# sch.net
KiCad netlist of a schematic drawn in EAGLE
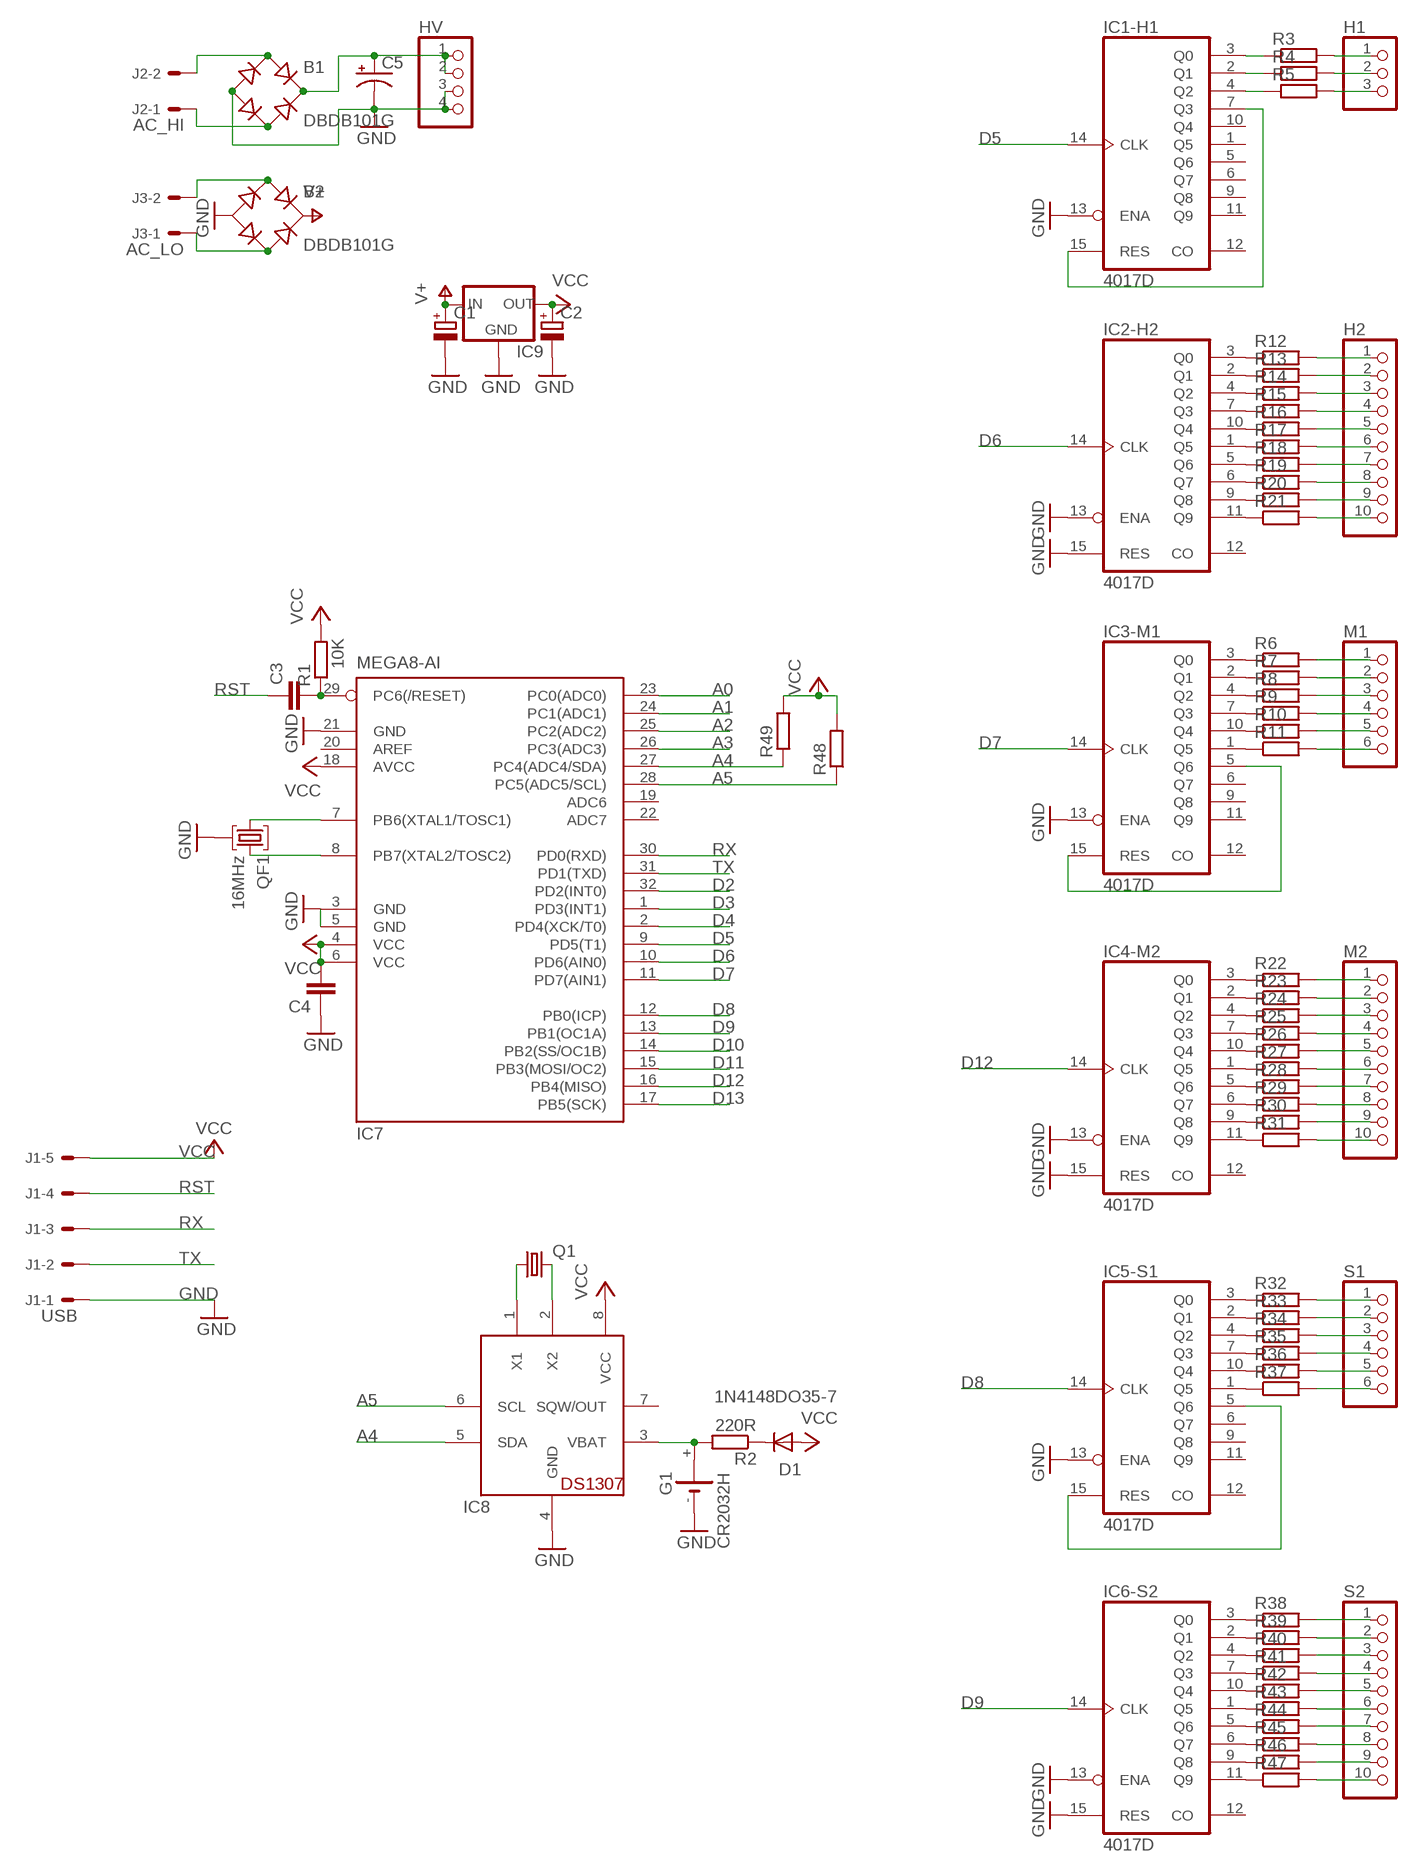
[diagram p0: schematic, sheet 1]

(export (version "E")
  (design (tool "Eeschema 10.0.6"))
  (components
    (comp (ref "B1")
      (value "DBDB101G")
      (footprint "eagle-import:DB")
      (libsource (lib "eagle-import") (part "DB?GDB101"))
    )
    (comp (ref "B2")
      (value "DBDB101G")
      (footprint "eagle-import:DB")
      (libsource (lib "eagle-import") (part "DB?GDB101"))
    )
    (comp (ref "C1")
      (value "CPOL-EU140CLH-1010")
      (footprint "eagle-import:140CLH-1010")
      (libsource (lib "eagle-import") (part "CPOL-EU140CLH-1010"))
    )
    (comp (ref "C2")
      (value "CPOL-EU140CLH-1010")
      (footprint "eagle-import:140CLH-1010")
      (libsource (lib "eagle-import") (part "CPOL-EU140CLH-1010"))
    )
    (comp (ref "C3")
      (value "C-EUC1206K")
      (footprint "eagle-import:C1206K")
      (libsource (lib "eagle-import") (part "C-EUC1206K"))
    )
    (comp (ref "C4")
      (value "C-EUC1206K")
      (footprint "eagle-import:C1206K")
      (libsource (lib "eagle-import") (part "C-EUC1206K"))
    )
    (comp (ref "C5")
      (value "CPOL-USE5-13")
      (footprint "eagle-import:E5-13")
      (libsource (lib "eagle-import") (part "CPOL-USE5-13"))
    )
    (comp (ref "D1")
      (value "1N4148DO35-7")
      (footprint "eagle-import:DO35-7")
      (libsource (lib "eagle-import") (part "1N4148DO35-7"))
    )
    (comp (ref "G1")
      (value "CR2032H")
      (footprint "eagle-import:CR2032H")
      (libsource (lib "eagle-import") (part "CR2032H"))
    )
    (comp (ref "H1")
      (value "PINHD-1X3")
      (footprint "eagle-import:1X03")
      (libsource (lib "eagle-import") (part "PINHD-1X3"))
    )
    (comp (ref "H2")
      (value "PINHD-1X10")
      (footprint "eagle-import:1X10")
      (libsource (lib "eagle-import") (part "PINHD-1X10"))
    )
    (comp (ref "HV")
      (value "PINHD-1X4")
      (footprint "eagle-import:1X04")
      (libsource (lib "eagle-import") (part "PINHD-1X4"))
    )
    (comp (ref "IC1-H1")
      (value "4017D")
      (footprint "eagle-import:SO16")
      (libsource (lib "eagle-import") (part "4017D"))
    )
    (comp (ref "IC2-H2")
      (value "4017D")
      (footprint "eagle-import:SO16")
      (libsource (lib "eagle-import") (part "4017D"))
    )
    (comp (ref "IC3-M1")
      (value "4017D")
      (footprint "eagle-import:SO16")
      (libsource (lib "eagle-import") (part "4017D"))
    )
    (comp (ref "IC4-M2")
      (value "4017D")
      (footprint "eagle-import:SO16")
      (libsource (lib "eagle-import") (part "4017D"))
    )
    (comp (ref "IC5-S1")
      (value "4017D")
      (footprint "eagle-import:SO16")
      (libsource (lib "eagle-import") (part "4017D"))
    )
    (comp (ref "IC6-S2")
      (value "4017D")
      (footprint "eagle-import:SO16")
      (libsource (lib "eagle-import") (part "4017D"))
    )
    (comp (ref "IC7")
      (value "MEGA8-AI")
      (footprint "eagle-import:TQFP32-08")
      (fields (field (name "MPN") "ATMEGA8-16AU"))
      (libsource (lib "eagle-import") (part "MEGA8-AI"))
    )
    (comp (ref "IC8")
      (value "DS1307")
      (footprint "eagle-import:DIL08")
      (libsource (lib "eagle-import") (part "DS1307"))
    )
    (comp (ref "IC9")
      (value "78XXS")
      (footprint "eagle-import:78XXS")
      (libsource (lib "eagle-import") (part "78XXS"))
    )
    (comp (ref "J1")
      (value "USB")
      (footprint "eagle-import:7395-05")
      (libsource (lib "eagle-import") (part "22-?-0505-7058"))
    )
    (comp (ref "J2")
      (value "AC_HI")
      (footprint "eagle-import:7395-02")
      (libsource (lib "eagle-import") (part "22-?-0205-7028"))
    )
    (comp (ref "J3")
      (value "AC_LO")
      (footprint "eagle-import:7395-02")
      (libsource (lib "eagle-import") (part "22-?-0205-7028"))
    )
    (comp (ref "M1")
      (value "PINHD-1X6")
      (footprint "eagle-import:1X06")
      (libsource (lib "eagle-import") (part "PINHD-1X6"))
    )
    (comp (ref "M2")
      (value "PINHD-1X10")
      (footprint "eagle-import:1X10")
      (libsource (lib "eagle-import") (part "PINHD-1X10"))
    )
    (comp (ref "Q1")
      (value "CRYSTALTC26H")
      (footprint "eagle-import:TC26H")
      (libsource (lib "eagle-import") (part "CRYSTALTC26H"))
    )
    (comp (ref "QF1")
      (value "16MHz")
      (footprint "eagle-import:HC49U")
      (libsource (lib "eagle-import") (part "8M10AHC49T"))
    )
    (comp (ref "R1")
      (value "10K")
      (footprint "eagle-import:0207_7")
      (libsource (lib "eagle-import") (part "R-EU_0207/7"))
    )
    (comp (ref "R2")
      (value "220R")
      (footprint "eagle-import:0207_7")
      (libsource (lib "eagle-import") (part "R-EU_0207/7"))
    )
    (comp (ref "R3")
      (value "R-EU_0204/5")
      (footprint "eagle-import:0204_5")
      (libsource (lib "eagle-import") (part "R-EU_0204/5"))
    )
    (comp (ref "R4")
      (value "R-EU_0204/5")
      (footprint "eagle-import:0204_5")
      (libsource (lib "eagle-import") (part "R-EU_0204/5"))
    )
    (comp (ref "R5")
      (value "R-EU_0204/5")
      (footprint "eagle-import:0204_5")
      (libsource (lib "eagle-import") (part "R-EU_0204/5"))
    )
    (comp (ref "R6")
      (value "R-EU_0204/5")
      (footprint "eagle-import:0204_5")
      (libsource (lib "eagle-import") (part "R-EU_0204/5"))
    )
    (comp (ref "R7")
      (value "R-EU_0204/5")
      (footprint "eagle-import:0204_5")
      (libsource (lib "eagle-import") (part "R-EU_0204/5"))
    )
    (comp (ref "R8")
      (value "R-EU_0204/5")
      (footprint "eagle-import:0204_5")
      (libsource (lib "eagle-import") (part "R-EU_0204/5"))
    )
    (comp (ref "R9")
      (value "R-EU_0204/5")
      (footprint "eagle-import:0204_5")
      (libsource (lib "eagle-import") (part "R-EU_0204/5"))
    )
    (comp (ref "R10")
      (value "R-EU_0204/5")
      (footprint "eagle-import:0204_5")
      (libsource (lib "eagle-import") (part "R-EU_0204/5"))
    )
    (comp (ref "R11")
      (value "R-EU_0204/5")
      (footprint "eagle-import:0204_5")
      (libsource (lib "eagle-import") (part "R-EU_0204/5"))
    )
    (comp (ref "R12")
      (value "R-EU_0204/5")
      (footprint "eagle-import:0204_5")
      (libsource (lib "eagle-import") (part "R-EU_0204/5"))
    )
    (comp (ref "R13")
      (value "R-EU_0204/5")
      (footprint "eagle-import:0204_5")
      (libsource (lib "eagle-import") (part "R-EU_0204/5"))
    )
    (comp (ref "R14")
      (value "R-EU_0204/5")
      (footprint "eagle-import:0204_5")
      (libsource (lib "eagle-import") (part "R-EU_0204/5"))
    )
    (comp (ref "R15")
      (value "R-EU_0204/5")
      (footprint "eagle-import:0204_5")
      (libsource (lib "eagle-import") (part "R-EU_0204/5"))
    )
    (comp (ref "R16")
      (value "R-EU_0204/5")
      (footprint "eagle-import:0204_5")
      (libsource (lib "eagle-import") (part "R-EU_0204/5"))
    )
    (comp (ref "R17")
      (value "R-EU_0204/5")
      (footprint "eagle-import:0204_5")
      (libsource (lib "eagle-import") (part "R-EU_0204/5"))
    )
    (comp (ref "R18")
      (value "R-EU_0204/5")
      (footprint "eagle-import:0204_5")
      (libsource (lib "eagle-import") (part "R-EU_0204/5"))
    )
    (comp (ref "R19")
      (value "R-EU_0204/5")
      (footprint "eagle-import:0204_5")
      (libsource (lib "eagle-import") (part "R-EU_0204/5"))
    )
    (comp (ref "R20")
      (value "R-EU_0204/5")
      (footprint "eagle-import:0204_5")
      (libsource (lib "eagle-import") (part "R-EU_0204/5"))
    )
    (comp (ref "R21")
      (value "R-EU_0204/5")
      (footprint "eagle-import:0204_5")
      (libsource (lib "eagle-import") (part "R-EU_0204/5"))
    )
    (comp (ref "R22")
      (value "R-EU_0204/5")
      (footprint "eagle-import:0204_5")
      (libsource (lib "eagle-import") (part "R-EU_0204/5"))
    )
    (comp (ref "R23")
      (value "R-EU_0204/5")
      (footprint "eagle-import:0204_5")
      (libsource (lib "eagle-import") (part "R-EU_0204/5"))
    )
    (comp (ref "R24")
      (value "R-EU_0204/5")
      (footprint "eagle-import:0204_5")
      (libsource (lib "eagle-import") (part "R-EU_0204/5"))
    )
    (comp (ref "R25")
      (value "R-EU_0204/5")
      (footprint "eagle-import:0204_5")
      (libsource (lib "eagle-import") (part "R-EU_0204/5"))
    )
    (comp (ref "R26")
      (value "R-EU_0204/5")
      (footprint "eagle-import:0204_5")
      (libsource (lib "eagle-import") (part "R-EU_0204/5"))
    )
    (comp (ref "R27")
      (value "R-EU_0204/5")
      (footprint "eagle-import:0204_5")
      (libsource (lib "eagle-import") (part "R-EU_0204/5"))
    )
    (comp (ref "R28")
      (value "R-EU_0204/5")
      (footprint "eagle-import:0204_5")
      (libsource (lib "eagle-import") (part "R-EU_0204/5"))
    )
    (comp (ref "R29")
      (value "R-EU_0204/5")
      (footprint "eagle-import:0204_5")
      (libsource (lib "eagle-import") (part "R-EU_0204/5"))
    )
    (comp (ref "R30")
      (value "R-EU_0204/5")
      (footprint "eagle-import:0204_5")
      (libsource (lib "eagle-import") (part "R-EU_0204/5"))
    )
    (comp (ref "R31")
      (value "R-EU_0204/5")
      (footprint "eagle-import:0204_5")
      (libsource (lib "eagle-import") (part "R-EU_0204/5"))
    )
    (comp (ref "R32")
      (value "R-EU_0204/5")
      (footprint "eagle-import:0204_5")
      (libsource (lib "eagle-import") (part "R-EU_0204/5"))
    )
    (comp (ref "R33")
      (value "R-EU_0204/5")
      (footprint "eagle-import:0204_5")
      (libsource (lib "eagle-import") (part "R-EU_0204/5"))
    )
    (comp (ref "R34")
      (value "R-EU_0204/5")
      (footprint "eagle-import:0204_5")
      (libsource (lib "eagle-import") (part "R-EU_0204/5"))
    )
    (comp (ref "R35")
      (value "R-EU_0204/5")
      (footprint "eagle-import:0204_5")
      (libsource (lib "eagle-import") (part "R-EU_0204/5"))
    )
    (comp (ref "R36")
      (value "R-EU_0204/5")
      (footprint "eagle-import:0204_5")
      (libsource (lib "eagle-import") (part "R-EU_0204/5"))
    )
    (comp (ref "R37")
      (value "R-EU_0204/5")
      (footprint "eagle-import:0204_5")
      (libsource (lib "eagle-import") (part "R-EU_0204/5"))
    )
    (comp (ref "R38")
      (value "R-EU_0204/5")
      (footprint "eagle-import:0204_5")
      (libsource (lib "eagle-import") (part "R-EU_0204/5"))
    )
    (comp (ref "R39")
      (value "R-EU_0204/5")
      (footprint "eagle-import:0204_5")
      (libsource (lib "eagle-import") (part "R-EU_0204/5"))
    )
    (comp (ref "R40")
      (value "R-EU_0204/5")
      (footprint "eagle-import:0204_5")
      (libsource (lib "eagle-import") (part "R-EU_0204/5"))
    )
    (comp (ref "R41")
      (value "R-EU_0204/5")
      (footprint "eagle-import:0204_5")
      (libsource (lib "eagle-import") (part "R-EU_0204/5"))
    )
    (comp (ref "R42")
      (value "R-EU_0204/5")
      (footprint "eagle-import:0204_5")
      (libsource (lib "eagle-import") (part "R-EU_0204/5"))
    )
    (comp (ref "R43")
      (value "R-EU_0204/5")
      (footprint "eagle-import:0204_5")
      (libsource (lib "eagle-import") (part "R-EU_0204/5"))
    )
    (comp (ref "R44")
      (value "R-EU_0204/5")
      (footprint "eagle-import:0204_5")
      (libsource (lib "eagle-import") (part "R-EU_0204/5"))
    )
    (comp (ref "R45")
      (value "R-EU_0204/5")
      (footprint "eagle-import:0204_5")
      (libsource (lib "eagle-import") (part "R-EU_0204/5"))
    )
    (comp (ref "R46")
      (value "R-EU_0204/5")
      (footprint "eagle-import:0204_5")
      (libsource (lib "eagle-import") (part "R-EU_0204/5"))
    )
    (comp (ref "R47")
      (value "R-EU_0204/5")
      (footprint "eagle-import:0204_5")
      (libsource (lib "eagle-import") (part "R-EU_0204/5"))
    )
    (comp (ref "R48")
      (value "R-EU_0204/5")
      (footprint "eagle-import:0204_5")
      (libsource (lib "eagle-import") (part "R-EU_0204/5"))
    )
    (comp (ref "R49")
      (value "R-EU_M1206")
      (footprint "eagle-import:M1206")
      (libsource (lib "eagle-import") (part "R-EU_M1206"))
    )
    (comp (ref "S1")
      (value "PINHD-1X6")
      (footprint "eagle-import:1X06")
      (libsource (lib "eagle-import") (part "PINHD-1X6"))
    )
    (comp (ref "S2")
      (value "PINHD-1X10")
      (footprint "eagle-import:1X10")
      (libsource (lib "eagle-import") (part "PINHD-1X10"))
    )
  )
  (nets
    (net (code "1") (name "/A0") (class "Default")
      (node (ref "IC7") (pin "23") (pinfunction "PC0(ADC0)_23") (pintype "bidirectional"))
    )
    (net (code "2") (name "/A1") (class "Default")
      (node (ref "IC7") (pin "24") (pinfunction "PC1(ADC1)_24") (pintype "bidirectional"))
    )
    (net (code "3") (name "/A2") (class "Default")
      (node (ref "IC7") (pin "25") (pinfunction "PC2(ADC2)_25") (pintype "bidirectional"))
    )
    (net (code "4") (name "/A3") (class "Default")
      (node (ref "IC7") (pin "26") (pinfunction "PC3(ADC3)_26") (pintype "bidirectional"))
    )
    (net (code "5") (name "/A4") (class "Default")
      (node (ref "IC7") (pin "27") (pinfunction "PC4(ADC4/SDA)_27") (pintype "bidirectional"))
      (node (ref "IC8") (pin "5") (pinfunction "SDA_5") (pintype "bidirectional"))
      (node (ref "R49") (pin "1") (pinfunction "1_1") (pintype "passive"))
    )
    (net (code "6") (name "/A5") (class "Default")
      (node (ref "IC7") (pin "28") (pinfunction "PC5(ADC5/SCL)_28") (pintype "bidirectional"))
      (node (ref "IC8") (pin "6") (pinfunction "SCL_6") (pintype "bidirectional"))
      (node (ref "R48") (pin "1") (pinfunction "1_1") (pintype "passive"))
    )
    (net (code "7") (name "/D2") (class "Default")
      (node (ref "IC7") (pin "32") (pinfunction "PD2(INT0)_32") (pintype "bidirectional"))
    )
    (net (code "8") (name "/D3") (class "Default")
      (node (ref "IC7") (pin "1") (pinfunction "PD3(INT1)_1") (pintype "bidirectional"))
    )
    (net (code "9") (name "/D4") (class "Default")
      (node (ref "IC7") (pin "2") (pinfunction "PD4(XCK/T0)_2") (pintype "bidirectional"))
    )
    (net (code "10") (name "/D5") (class "Default")
      (node (ref "IC1-H1") (pin "14") (pinfunction "CLK_14") (pintype "input"))
      (node (ref "IC7") (pin "9") (pinfunction "PD5(T1)_9") (pintype "bidirectional"))
    )
    (net (code "11") (name "/D6") (class "Default")
      (node (ref "IC2-H2") (pin "14") (pinfunction "CLK_14") (pintype "input"))
      (node (ref "IC7") (pin "10") (pinfunction "PD6(AIN0)_10") (pintype "bidirectional"))
    )
    (net (code "12") (name "/D7") (class "Default")
      (node (ref "IC3-M1") (pin "14") (pinfunction "CLK_14") (pintype "input"))
      (node (ref "IC7") (pin "11") (pinfunction "PD7(AIN1)_11") (pintype "bidirectional"))
    )
    (net (code "13") (name "/D8") (class "Default")
      (node (ref "IC5-S1") (pin "14") (pinfunction "CLK_14") (pintype "input"))
      (node (ref "IC7") (pin "12") (pinfunction "PB0(ICP)_12") (pintype "bidirectional"))
    )
    (net (code "14") (name "/D9") (class "Default")
      (node (ref "IC6-S2") (pin "14") (pinfunction "CLK_14") (pintype "input"))
      (node (ref "IC7") (pin "13") (pinfunction "PB1(OC1A)_13") (pintype "bidirectional"))
    )
    (net (code "15") (name "/D10") (class "Default")
      (node (ref "IC7") (pin "14") (pinfunction "PB2(SS/OC1B)_14") (pintype "bidirectional"))
    )
    (net (code "16") (name "/D11") (class "Default")
      (node (ref "IC7") (pin "15") (pinfunction "PB3(MOSI/OC2)_15") (pintype "bidirectional"))
    )
    (net (code "17") (name "/D12") (class "Default")
      (node (ref "IC4-M2") (pin "14") (pinfunction "CLK_14") (pintype "input"))
      (node (ref "IC7") (pin "16") (pinfunction "PB4(MISO)_16") (pintype "bidirectional"))
    )
    (net (code "18") (name "/D13") (class "Default")
      (node (ref "IC7") (pin "17") (pinfunction "PB5(SCK)_17") (pintype "bidirectional"))
    )
    (net (code "19") (name "/RST") (class "Default")
      (node (ref "C3") (pin "1") (pinfunction "1_1") (pintype "passive"))
      (node (ref "J1") (pin "4") (pinfunction "S_4") (pintype "passive"))
    )
    (net (code "20") (name "/RX") (class "Default")
      (node (ref "IC7") (pin "30") (pinfunction "PD0(RXD)_30") (pintype "bidirectional"))
      (node (ref "J1") (pin "3") (pinfunction "S_3") (pintype "passive"))
    )
    (net (code "21") (name "/TX") (class "Default")
      (node (ref "IC7") (pin "31") (pinfunction "PD1(TXD)_31") (pintype "bidirectional"))
      (node (ref "J1") (pin "2") (pinfunction "S_2") (pintype "passive"))
    )
    (net (code "22") (name "GND") (class "Default")
      (node (ref "B1") (pin "-") (pinfunction "-_-") (pintype "passive"))
      (node (ref "B2") (pin "-") (pinfunction "-_-") (pintype "passive"))
      (node (ref "C1") (pin "-") (pinfunction "-_-") (pintype "passive"))
      (node (ref "C2") (pin "-") (pinfunction "-_-") (pintype "passive"))
      (node (ref "C4") (pin "1") (pinfunction "1_1") (pintype "passive"))
      (node (ref "C5") (pin "-") (pinfunction "-_-") (pintype "passive"))
      (node (ref "G1") (pin "-") (pinfunction "-_-") (pintype "passive"))
      (node (ref "HV") (pin "3") (pinfunction "3_3") (pintype "passive"))
      (node (ref "HV") (pin "4") (pinfunction "4_4") (pintype "passive"))
      (node (ref "IC1-H1") (pin "13") (pinfunction "ENA_13") (pintype "input"))
      (node (ref "IC2-H2") (pin "13") (pinfunction "ENA_13") (pintype "input"))
      (node (ref "IC2-H2") (pin "15") (pinfunction "RES_15") (pintype "input"))
      (node (ref "IC3-M1") (pin "13") (pinfunction "ENA_13") (pintype "input"))
      (node (ref "IC4-M2") (pin "13") (pinfunction "ENA_13") (pintype "input"))
      (node (ref "IC4-M2") (pin "15") (pinfunction "RES_15") (pintype "input"))
      (node (ref "IC5-S1") (pin "13") (pinfunction "ENA_13") (pintype "input"))
      (node (ref "IC6-S2") (pin "13") (pinfunction "ENA_13") (pintype "input"))
      (node (ref "IC6-S2") (pin "15") (pinfunction "RES_15") (pintype "input"))
      (node (ref "IC7") (pin "21") (pinfunction "GND_21") (pintype "power_in"))
      (node (ref "IC7") (pin "3") (pinfunction "GND_3") (pintype "power_in"))
      (node (ref "IC7") (pin "5") (pinfunction "GND_5") (pintype "power_in"))
      (node (ref "IC8") (pin "4") (pinfunction "GND_4") (pintype "power_in"))
      (node (ref "IC9") (pin "GND") (pinfunction "GND_GND") (pintype "input"))
      (node (ref "J1") (pin "1") (pinfunction "S_1") (pintype "passive"))
      (node (ref "QF1") (pin "2") (pinfunction "2_2") (pintype "passive"))
    )
    (net (code "23") (name "Net-(B1-Pad+)") (class "Default")
      (node (ref "B1") (pin "+") (pinfunction "+_+") (pintype "passive"))
      (node (ref "C5") (pin "+") (pinfunction "+_+") (pintype "passive"))
      (node (ref "HV") (pin "1") (pinfunction "1_1") (pintype "passive"))
      (node (ref "HV") (pin "2") (pinfunction "2_2") (pintype "passive"))
    )
    (net (code "24") (name "Net-(D1-PadC)") (class "Default")
      (node (ref "D1") (pin "C") (pinfunction "C_C") (pintype "passive"))
      (node (ref "R2") (pin "1") (pinfunction "1_1") (pintype "passive"))
    )
    (net (code "25") (name "Net-(H1-Pad1)") (class "Default")
      (node (ref "H1") (pin "1") (pinfunction "1_1") (pintype "passive"))
      (node (ref "R3") (pin "2") (pinfunction "2_2") (pintype "passive"))
    )
    (net (code "26") (name "Net-(H1-Pad2)") (class "Default")
      (node (ref "H1") (pin "2") (pinfunction "2_2") (pintype "passive"))
      (node (ref "R4") (pin "2") (pinfunction "2_2") (pintype "passive"))
    )
    (net (code "27") (name "Net-(H1-Pad3)") (class "Default")
      (node (ref "H1") (pin "3") (pinfunction "3_3") (pintype "passive"))
      (node (ref "R5") (pin "2") (pinfunction "2_2") (pintype "passive"))
    )
    (net (code "28") (name "Net-(H2-Pad1)") (class "Default")
      (node (ref "H2") (pin "1") (pinfunction "1_1") (pintype "passive"))
      (node (ref "R12") (pin "2") (pinfunction "2_2") (pintype "passive"))
    )
    (net (code "29") (name "Net-(H2-Pad2)") (class "Default")
      (node (ref "H2") (pin "2") (pinfunction "2_2") (pintype "passive"))
      (node (ref "R13") (pin "2") (pinfunction "2_2") (pintype "passive"))
    )
    (net (code "30") (name "Net-(H2-Pad3)") (class "Default")
      (node (ref "H2") (pin "3") (pinfunction "3_3") (pintype "passive"))
      (node (ref "R14") (pin "2") (pinfunction "2_2") (pintype "passive"))
    )
    (net (code "31") (name "Net-(H2-Pad4)") (class "Default")
      (node (ref "H2") (pin "4") (pinfunction "4_4") (pintype "passive"))
      (node (ref "R15") (pin "2") (pinfunction "2_2") (pintype "passive"))
    )
    (net (code "32") (name "Net-(H2-Pad5)") (class "Default")
      (node (ref "H2") (pin "5") (pinfunction "5_5") (pintype "passive"))
      (node (ref "R16") (pin "2") (pinfunction "2_2") (pintype "passive"))
    )
    (net (code "33") (name "Net-(H2-Pad6)") (class "Default")
      (node (ref "H2") (pin "6") (pinfunction "6_6") (pintype "passive"))
      (node (ref "R17") (pin "2") (pinfunction "2_2") (pintype "passive"))
    )
    (net (code "34") (name "Net-(H2-Pad7)") (class "Default")
      (node (ref "H2") (pin "7") (pinfunction "7_7") (pintype "passive"))
      (node (ref "R18") (pin "2") (pinfunction "2_2") (pintype "passive"))
    )
    (net (code "35") (name "Net-(H2-Pad8)") (class "Default")
      (node (ref "H2") (pin "8") (pinfunction "8_8") (pintype "passive"))
      (node (ref "R19") (pin "2") (pinfunction "2_2") (pintype "passive"))
    )
    (net (code "36") (name "Net-(H2-Pad9)") (class "Default")
      (node (ref "H2") (pin "9") (pinfunction "9_9") (pintype "passive"))
      (node (ref "R20") (pin "2") (pinfunction "2_2") (pintype "passive"))
    )
    (net (code "37") (name "Net-(H2-Pad10)") (class "Default")
      (node (ref "H2") (pin "10") (pinfunction "10_10") (pintype "passive"))
      (node (ref "R21") (pin "2") (pinfunction "2_2") (pintype "passive"))
    )
    (net (code "38") (name "Net-(IC1-H1A-Q0)") (class "Default")
      (node (ref "IC1-H1") (pin "3") (pinfunction "Q0_3") (pintype "output"))
      (node (ref "R3") (pin "1") (pinfunction "1_1") (pintype "passive"))
    )
    (net (code "39") (name "Net-(IC1-H1A-Q1)") (class "Default")
      (node (ref "IC1-H1") (pin "2") (pinfunction "Q1_2") (pintype "output"))
      (node (ref "R4") (pin "1") (pinfunction "1_1") (pintype "passive"))
    )
    (net (code "40") (name "Net-(IC1-H1A-Q2)") (class "Default")
      (node (ref "IC1-H1") (pin "4") (pinfunction "Q2_4") (pintype "output"))
      (node (ref "R5") (pin "1") (pinfunction "1_1") (pintype "passive"))
    )
    (net (code "41") (name "Net-(IC1-H1A-Q3)") (class "Default")
      (node (ref "IC1-H1") (pin "15") (pinfunction "RES_15") (pintype "input"))
      (node (ref "IC1-H1") (pin "7") (pinfunction "Q3_7") (pintype "output"))
    )
    (net (code "42") (name "Net-(IC2-H2A-Q0)") (class "Default")
      (node (ref "IC2-H2") (pin "3") (pinfunction "Q0_3") (pintype "output"))
      (node (ref "R12") (pin "1") (pinfunction "1_1") (pintype "passive"))
    )
    (net (code "43") (name "Net-(IC2-H2A-Q1)") (class "Default")
      (node (ref "IC2-H2") (pin "2") (pinfunction "Q1_2") (pintype "output"))
      (node (ref "R13") (pin "1") (pinfunction "1_1") (pintype "passive"))
    )
    (net (code "44") (name "Net-(IC2-H2A-Q2)") (class "Default")
      (node (ref "IC2-H2") (pin "4") (pinfunction "Q2_4") (pintype "output"))
      (node (ref "R14") (pin "1") (pinfunction "1_1") (pintype "passive"))
    )
    (net (code "45") (name "Net-(IC2-H2A-Q3)") (class "Default")
      (node (ref "IC2-H2") (pin "7") (pinfunction "Q3_7") (pintype "output"))
      (node (ref "R15") (pin "1") (pinfunction "1_1") (pintype "passive"))
    )
    (net (code "46") (name "Net-(IC2-H2A-Q4)") (class "Default")
      (node (ref "IC2-H2") (pin "10") (pinfunction "Q4_10") (pintype "output"))
      (node (ref "R16") (pin "1") (pinfunction "1_1") (pintype "passive"))
    )
    (net (code "47") (name "Net-(IC2-H2A-Q5)") (class "Default")
      (node (ref "IC2-H2") (pin "1") (pinfunction "Q5_1") (pintype "output"))
      (node (ref "R17") (pin "1") (pinfunction "1_1") (pintype "passive"))
    )
    (net (code "48") (name "Net-(IC2-H2A-Q6)") (class "Default")
      (node (ref "IC2-H2") (pin "5") (pinfunction "Q6_5") (pintype "output"))
      (node (ref "R18") (pin "1") (pinfunction "1_1") (pintype "passive"))
    )
    (net (code "49") (name "Net-(IC2-H2A-Q7)") (class "Default")
      (node (ref "IC2-H2") (pin "6") (pinfunction "Q7_6") (pintype "output"))
      (node (ref "R19") (pin "1") (pinfunction "1_1") (pintype "passive"))
    )
    (net (code "50") (name "Net-(IC2-H2A-Q8)") (class "Default")
      (node (ref "IC2-H2") (pin "9") (pinfunction "Q8_9") (pintype "output"))
      (node (ref "R20") (pin "1") (pinfunction "1_1") (pintype "passive"))
    )
    (net (code "51") (name "Net-(IC2-H2A-Q9)") (class "Default")
      (node (ref "IC2-H2") (pin "11") (pinfunction "Q9_11") (pintype "output"))
      (node (ref "R21") (pin "1") (pinfunction "1_1") (pintype "passive"))
    )
    (net (code "52") (name "Net-(IC3-M1A-Q0)") (class "Default")
      (node (ref "IC3-M1") (pin "3") (pinfunction "Q0_3") (pintype "output"))
      (node (ref "R6") (pin "1") (pinfunction "1_1") (pintype "passive"))
    )
    (net (code "53") (name "Net-(IC3-M1A-Q1)") (class "Default")
      (node (ref "IC3-M1") (pin "2") (pinfunction "Q1_2") (pintype "output"))
      (node (ref "R7") (pin "1") (pinfunction "1_1") (pintype "passive"))
    )
    (net (code "54") (name "Net-(IC3-M1A-Q2)") (class "Default")
      (node (ref "IC3-M1") (pin "4") (pinfunction "Q2_4") (pintype "output"))
      (node (ref "R8") (pin "1") (pinfunction "1_1") (pintype "passive"))
    )
    (net (code "55") (name "Net-(IC3-M1A-Q3)") (class "Default")
      (node (ref "IC3-M1") (pin "7") (pinfunction "Q3_7") (pintype "output"))
      (node (ref "R9") (pin "1") (pinfunction "1_1") (pintype "passive"))
    )
    (net (code "56") (name "Net-(IC3-M1A-Q4)") (class "Default")
      (node (ref "IC3-M1") (pin "10") (pinfunction "Q4_10") (pintype "output"))
      (node (ref "R10") (pin "1") (pinfunction "1_1") (pintype "passive"))
    )
    (net (code "57") (name "Net-(IC3-M1A-Q5)") (class "Default")
      (node (ref "IC3-M1") (pin "1") (pinfunction "Q5_1") (pintype "output"))
      (node (ref "R11") (pin "1") (pinfunction "1_1") (pintype "passive"))
    )
    (net (code "58") (name "Net-(IC3-M1A-Q6)") (class "Default")
      (node (ref "IC3-M1") (pin "15") (pinfunction "RES_15") (pintype "input"))
      (node (ref "IC3-M1") (pin "5") (pinfunction "Q6_5") (pintype "output"))
    )
    (net (code "59") (name "Net-(IC4-M2A-Q0)") (class "Default")
      (node (ref "IC4-M2") (pin "3") (pinfunction "Q0_3") (pintype "output"))
      (node (ref "R22") (pin "1") (pinfunction "1_1") (pintype "passive"))
    )
    (net (code "60") (name "Net-(IC4-M2A-Q1)") (class "Default")
      (node (ref "IC4-M2") (pin "2") (pinfunction "Q1_2") (pintype "output"))
      (node (ref "R23") (pin "1") (pinfunction "1_1") (pintype "passive"))
    )
    (net (code "61") (name "Net-(IC4-M2A-Q2)") (class "Default")
      (node (ref "IC4-M2") (pin "4") (pinfunction "Q2_4") (pintype "output"))
      (node (ref "R24") (pin "1") (pinfunction "1_1") (pintype "passive"))
    )
    (net (code "62") (name "Net-(IC4-M2A-Q3)") (class "Default")
      (node (ref "IC4-M2") (pin "7") (pinfunction "Q3_7") (pintype "output"))
      (node (ref "R25") (pin "1") (pinfunction "1_1") (pintype "passive"))
    )
    (net (code "63") (name "Net-(IC4-M2A-Q4)") (class "Default")
      (node (ref "IC4-M2") (pin "10") (pinfunction "Q4_10") (pintype "output"))
      (node (ref "R26") (pin "1") (pinfunction "1_1") (pintype "passive"))
    )
    (net (code "64") (name "Net-(IC4-M2A-Q5)") (class "Default")
      (node (ref "IC4-M2") (pin "1") (pinfunction "Q5_1") (pintype "output"))
      (node (ref "R27") (pin "1") (pinfunction "1_1") (pintype "passive"))
    )
    (net (code "65") (name "Net-(IC4-M2A-Q6)") (class "Default")
      (node (ref "IC4-M2") (pin "5") (pinfunction "Q6_5") (pintype "output"))
      (node (ref "R28") (pin "1") (pinfunction "1_1") (pintype "passive"))
    )
    (net (code "66") (name "Net-(IC4-M2A-Q7)") (class "Default")
      (node (ref "IC4-M2") (pin "6") (pinfunction "Q7_6") (pintype "output"))
      (node (ref "R29") (pin "1") (pinfunction "1_1") (pintype "passive"))
    )
    (net (code "67") (name "Net-(IC4-M2A-Q8)") (class "Default")
      (node (ref "IC4-M2") (pin "9") (pinfunction "Q8_9") (pintype "output"))
      (node (ref "R30") (pin "1") (pinfunction "1_1") (pintype "passive"))
    )
    (net (code "68") (name "Net-(IC4-M2A-Q9)") (class "Default")
      (node (ref "IC4-M2") (pin "11") (pinfunction "Q9_11") (pintype "output"))
      (node (ref "R31") (pin "1") (pinfunction "1_1") (pintype "passive"))
    )
    (net (code "69") (name "Net-(IC5-S1A-Q0)") (class "Default")
      (node (ref "IC5-S1") (pin "3") (pinfunction "Q0_3") (pintype "output"))
      (node (ref "R32") (pin "1") (pinfunction "1_1") (pintype "passive"))
    )
    (net (code "70") (name "Net-(IC5-S1A-Q1)") (class "Default")
      (node (ref "IC5-S1") (pin "2") (pinfunction "Q1_2") (pintype "output"))
      (node (ref "R33") (pin "1") (pinfunction "1_1") (pintype "passive"))
    )
    (net (code "71") (name "Net-(IC5-S1A-Q2)") (class "Default")
      (node (ref "IC5-S1") (pin "4") (pinfunction "Q2_4") (pintype "output"))
      (node (ref "R34") (pin "1") (pinfunction "1_1") (pintype "passive"))
    )
    (net (code "72") (name "Net-(IC5-S1A-Q3)") (class "Default")
      (node (ref "IC5-S1") (pin "7") (pinfunction "Q3_7") (pintype "output"))
      (node (ref "R35") (pin "1") (pinfunction "1_1") (pintype "passive"))
    )
    (net (code "73") (name "Net-(IC5-S1A-Q4)") (class "Default")
      (node (ref "IC5-S1") (pin "10") (pinfunction "Q4_10") (pintype "output"))
      (node (ref "R36") (pin "1") (pinfunction "1_1") (pintype "passive"))
    )
    (net (code "74") (name "Net-(IC5-S1A-Q5)") (class "Default")
      (node (ref "IC5-S1") (pin "1") (pinfunction "Q5_1") (pintype "output"))
      (node (ref "R37") (pin "1") (pinfunction "1_1") (pintype "passive"))
    )
    (net (code "75") (name "Net-(IC5-S1A-Q6)") (class "Default")
      (node (ref "IC5-S1") (pin "15") (pinfunction "RES_15") (pintype "input"))
      (node (ref "IC5-S1") (pin "5") (pinfunction "Q6_5") (pintype "output"))
    )
    (net (code "76") (name "Net-(IC6-S2A-Q0)") (class "Default")
      (node (ref "IC6-S2") (pin "3") (pinfunction "Q0_3") (pintype "output"))
      (node (ref "R38") (pin "1") (pinfunction "1_1") (pintype "passive"))
    )
    (net (code "77") (name "Net-(IC6-S2A-Q1)") (class "Default")
      (node (ref "IC6-S2") (pin "2") (pinfunction "Q1_2") (pintype "output"))
      (node (ref "R39") (pin "1") (pinfunction "1_1") (pintype "passive"))
    )
    (net (code "78") (name "Net-(IC6-S2A-Q2)") (class "Default")
      (node (ref "IC6-S2") (pin "4") (pinfunction "Q2_4") (pintype "output"))
      (node (ref "R40") (pin "1") (pinfunction "1_1") (pintype "passive"))
    )
    (net (code "79") (name "Net-(IC6-S2A-Q3)") (class "Default")
      (node (ref "IC6-S2") (pin "7") (pinfunction "Q3_7") (pintype "output"))
      (node (ref "R41") (pin "1") (pinfunction "1_1") (pintype "passive"))
    )
    (net (code "80") (name "Net-(IC6-S2A-Q4)") (class "Default")
      (node (ref "IC6-S2") (pin "10") (pinfunction "Q4_10") (pintype "output"))
      (node (ref "R42") (pin "1") (pinfunction "1_1") (pintype "passive"))
    )
    (net (code "81") (name "Net-(IC6-S2A-Q5)") (class "Default")
      (node (ref "IC6-S2") (pin "1") (pinfunction "Q5_1") (pintype "output"))
      (node (ref "R43") (pin "1") (pinfunction "1_1") (pintype "passive"))
    )
    (net (code "82") (name "Net-(IC6-S2A-Q6)") (class "Default")
      (node (ref "IC6-S2") (pin "5") (pinfunction "Q6_5") (pintype "output"))
      (node (ref "R44") (pin "1") (pinfunction "1_1") (pintype "passive"))
    )
    (net (code "83") (name "Net-(IC6-S2A-Q7)") (class "Default")
      (node (ref "IC6-S2") (pin "6") (pinfunction "Q7_6") (pintype "output"))
      (node (ref "R45") (pin "1") (pinfunction "1_1") (pintype "passive"))
    )
    (net (code "84") (name "Net-(IC6-S2A-Q8)") (class "Default")
      (node (ref "IC6-S2") (pin "9") (pinfunction "Q8_9") (pintype "output"))
      (node (ref "R46") (pin "1") (pinfunction "1_1") (pintype "passive"))
    )
    (net (code "85") (name "Net-(IC6-S2A-Q9)") (class "Default")
      (node (ref "IC6-S2") (pin "11") (pinfunction "Q9_11") (pintype "output"))
      (node (ref "R47") (pin "1") (pinfunction "1_1") (pintype "passive"))
    )
    (net (code "86") (name "Net-(IC7-PB6(XTAL1{slash}TOSC1))") (class "Default")
      (node (ref "IC7") (pin "7") (pinfunction "PB6(XTAL1/TOSC1)_7") (pintype "bidirectional"))
      (node (ref "QF1") (pin "1") (pinfunction "1_1") (pintype "passive"))
    )
    (net (code "87") (name "Net-(IC7-PB7(XTAL2{slash}TOSC2))") (class "Default")
      (node (ref "IC7") (pin "8") (pinfunction "PB7(XTAL2/TOSC2)_8") (pintype "bidirectional"))
      (node (ref "QF1") (pin "3") (pinfunction "3_3") (pintype "passive"))
    )
    (net (code "88") (name "Net-(IC7-PC6({slash}RESET))") (class "Default")
      (node (ref "C3") (pin "2") (pinfunction "2_2") (pintype "passive"))
      (node (ref "IC7") (pin "29") (pinfunction "PC6(/RESET)_29") (pintype "bidirectional"))
      (node (ref "R1") (pin "1") (pinfunction "1_1") (pintype "passive"))
    )
    (net (code "89") (name "Net-(IC8-VBAT)") (class "Default")
      (node (ref "G1") (pin "+") (pinfunction "+_+") (pintype "passive"))
      (node (ref "IC8") (pin "3") (pinfunction "VBAT_3") (pintype "power_in"))
      (node (ref "R2") (pin "2") (pinfunction "2_2") (pintype "passive"))
    )
    (net (code "90") (name "Net-(IC8-X1)") (class "Default")
      (node (ref "IC8") (pin "1") (pinfunction "X1_1") (pintype "passive"))
      (node (ref "Q1") (pin "1") (pinfunction "1_1") (pintype "passive"))
    )
    (net (code "91") (name "Net-(IC8-X2)") (class "Default")
      (node (ref "IC8") (pin "2") (pinfunction "X2_2") (pintype "passive"))
      (node (ref "Q1") (pin "2") (pinfunction "2_2") (pintype "passive"))
    )
    (net (code "92") (name "Net-(J2A-S)") (class "Default")
      (node (ref "B1") (pin "AC2") (pinfunction "AC2_AC2") (pintype "passive"))
      (node (ref "J2") (pin "1") (pinfunction "S_1") (pintype "passive"))
    )
    (net (code "93") (name "Net-(J2B-S)") (class "Default")
      (node (ref "B1") (pin "AC1") (pinfunction "AC1_AC1") (pintype "passive"))
      (node (ref "J2") (pin "2") (pinfunction "S_2") (pintype "passive"))
    )
    (net (code "94") (name "Net-(J3A-S)") (class "Default")
      (node (ref "B2") (pin "AC2") (pinfunction "AC2_AC2") (pintype "passive"))
      (node (ref "J3") (pin "1") (pinfunction "S_1") (pintype "passive"))
    )
    (net (code "95") (name "Net-(J3B-S)") (class "Default")
      (node (ref "B2") (pin "AC1") (pinfunction "AC1_AC1") (pintype "passive"))
      (node (ref "J3") (pin "2") (pinfunction "S_2") (pintype "passive"))
    )
    (net (code "96") (name "Net-(M1-Pad1)") (class "Default")
      (node (ref "M1") (pin "1") (pinfunction "1_1") (pintype "passive"))
      (node (ref "R6") (pin "2") (pinfunction "2_2") (pintype "passive"))
    )
    (net (code "97") (name "Net-(M1-Pad2)") (class "Default")
      (node (ref "M1") (pin "2") (pinfunction "2_2") (pintype "passive"))
      (node (ref "R7") (pin "2") (pinfunction "2_2") (pintype "passive"))
    )
    (net (code "98") (name "Net-(M1-Pad3)") (class "Default")
      (node (ref "M1") (pin "3") (pinfunction "3_3") (pintype "passive"))
      (node (ref "R8") (pin "2") (pinfunction "2_2") (pintype "passive"))
    )
    (net (code "99") (name "Net-(M1-Pad4)") (class "Default")
      (node (ref "M1") (pin "4") (pinfunction "4_4") (pintype "passive"))
      (node (ref "R9") (pin "2") (pinfunction "2_2") (pintype "passive"))
    )
    (net (code "100") (name "Net-(M1-Pad5)") (class "Default")
      (node (ref "M1") (pin "5") (pinfunction "5_5") (pintype "passive"))
      (node (ref "R10") (pin "2") (pinfunction "2_2") (pintype "passive"))
    )
    (net (code "101") (name "Net-(M1-Pad6)") (class "Default")
      (node (ref "M1") (pin "6") (pinfunction "6_6") (pintype "passive"))
      (node (ref "R11") (pin "2") (pinfunction "2_2") (pintype "passive"))
    )
    (net (code "102") (name "Net-(M2-Pad1)") (class "Default")
      (node (ref "M2") (pin "1") (pinfunction "1_1") (pintype "passive"))
      (node (ref "R22") (pin "2") (pinfunction "2_2") (pintype "passive"))
    )
    (net (code "103") (name "Net-(M2-Pad2)") (class "Default")
      (node (ref "M2") (pin "2") (pinfunction "2_2") (pintype "passive"))
      (node (ref "R23") (pin "2") (pinfunction "2_2") (pintype "passive"))
    )
    (net (code "104") (name "Net-(M2-Pad3)") (class "Default")
      (node (ref "M2") (pin "3") (pinfunction "3_3") (pintype "passive"))
      (node (ref "R24") (pin "2") (pinfunction "2_2") (pintype "passive"))
    )
    (net (code "105") (name "Net-(M2-Pad4)") (class "Default")
      (node (ref "M2") (pin "4") (pinfunction "4_4") (pintype "passive"))
      (node (ref "R25") (pin "2") (pinfunction "2_2") (pintype "passive"))
    )
    (net (code "106") (name "Net-(M2-Pad5)") (class "Default")
      (node (ref "M2") (pin "5") (pinfunction "5_5") (pintype "passive"))
      (node (ref "R26") (pin "2") (pinfunction "2_2") (pintype "passive"))
    )
    (net (code "107") (name "Net-(M2-Pad6)") (class "Default")
      (node (ref "M2") (pin "6") (pinfunction "6_6") (pintype "passive"))
      (node (ref "R27") (pin "2") (pinfunction "2_2") (pintype "passive"))
    )
    (net (code "108") (name "Net-(M2-Pad7)") (class "Default")
      (node (ref "M2") (pin "7") (pinfunction "7_7") (pintype "passive"))
      (node (ref "R28") (pin "2") (pinfunction "2_2") (pintype "passive"))
    )
    (net (code "109") (name "Net-(M2-Pad8)") (class "Default")
      (node (ref "M2") (pin "8") (pinfunction "8_8") (pintype "passive"))
      (node (ref "R29") (pin "2") (pinfunction "2_2") (pintype "passive"))
    )
    (net (code "110") (name "Net-(M2-Pad9)") (class "Default")
      (node (ref "M2") (pin "9") (pinfunction "9_9") (pintype "passive"))
      (node (ref "R30") (pin "2") (pinfunction "2_2") (pintype "passive"))
    )
    (net (code "111") (name "Net-(M2-Pad10)") (class "Default")
      (node (ref "M2") (pin "10") (pinfunction "10_10") (pintype "passive"))
      (node (ref "R31") (pin "2") (pinfunction "2_2") (pintype "passive"))
    )
    (net (code "112") (name "Net-(R32-Pad2)") (class "Default")
      (node (ref "R32") (pin "2") (pinfunction "2_2") (pintype "passive"))
      (node (ref "S1") (pin "1") (pinfunction "1_1") (pintype "passive"))
    )
    (net (code "113") (name "Net-(R33-Pad2)") (class "Default")
      (node (ref "R33") (pin "2") (pinfunction "2_2") (pintype "passive"))
      (node (ref "S1") (pin "2") (pinfunction "2_2") (pintype "passive"))
    )
    (net (code "114") (name "Net-(R34-Pad2)") (class "Default")
      (node (ref "R34") (pin "2") (pinfunction "2_2") (pintype "passive"))
      (node (ref "S1") (pin "3") (pinfunction "3_3") (pintype "passive"))
    )
    (net (code "115") (name "Net-(R35-Pad2)") (class "Default")
      (node (ref "R35") (pin "2") (pinfunction "2_2") (pintype "passive"))
      (node (ref "S1") (pin "4") (pinfunction "4_4") (pintype "passive"))
    )
    (net (code "116") (name "Net-(R36-Pad2)") (class "Default")
      (node (ref "R36") (pin "2") (pinfunction "2_2") (pintype "passive"))
      (node (ref "S1") (pin "5") (pinfunction "5_5") (pintype "passive"))
    )
    (net (code "117") (name "Net-(R37-Pad2)") (class "Default")
      (node (ref "R37") (pin "2") (pinfunction "2_2") (pintype "passive"))
      (node (ref "S1") (pin "6") (pinfunction "6_6") (pintype "passive"))
    )
    (net (code "118") (name "Net-(R38-Pad2)") (class "Default")
      (node (ref "R38") (pin "2") (pinfunction "2_2") (pintype "passive"))
      (node (ref "S2") (pin "1") (pinfunction "1_1") (pintype "passive"))
    )
    (net (code "119") (name "Net-(R39-Pad2)") (class "Default")
      (node (ref "R39") (pin "2") (pinfunction "2_2") (pintype "passive"))
      (node (ref "S2") (pin "2") (pinfunction "2_2") (pintype "passive"))
    )
    (net (code "120") (name "Net-(R40-Pad2)") (class "Default")
      (node (ref "R40") (pin "2") (pinfunction "2_2") (pintype "passive"))
      (node (ref "S2") (pin "3") (pinfunction "3_3") (pintype "passive"))
    )
    (net (code "121") (name "Net-(R41-Pad2)") (class "Default")
      (node (ref "R41") (pin "2") (pinfunction "2_2") (pintype "passive"))
      (node (ref "S2") (pin "4") (pinfunction "4_4") (pintype "passive"))
    )
    (net (code "122") (name "Net-(R42-Pad2)") (class "Default")
      (node (ref "R42") (pin "2") (pinfunction "2_2") (pintype "passive"))
      (node (ref "S2") (pin "5") (pinfunction "5_5") (pintype "passive"))
    )
    (net (code "123") (name "Net-(R43-Pad2)") (class "Default")
      (node (ref "R43") (pin "2") (pinfunction "2_2") (pintype "passive"))
      (node (ref "S2") (pin "6") (pinfunction "6_6") (pintype "passive"))
    )
    (net (code "124") (name "Net-(R44-Pad2)") (class "Default")
      (node (ref "R44") (pin "2") (pinfunction "2_2") (pintype "passive"))
      (node (ref "S2") (pin "7") (pinfunction "7_7") (pintype "passive"))
    )
    (net (code "125") (name "Net-(R45-Pad2)") (class "Default")
      (node (ref "R45") (pin "2") (pinfunction "2_2") (pintype "passive"))
      (node (ref "S2") (pin "8") (pinfunction "8_8") (pintype "passive"))
    )
    (net (code "126") (name "Net-(R46-Pad2)") (class "Default")
      (node (ref "R46") (pin "2") (pinfunction "2_2") (pintype "passive"))
      (node (ref "S2") (pin "9") (pinfunction "9_9") (pintype "passive"))
    )
    (net (code "127") (name "Net-(R47-Pad2)") (class "Default")
      (node (ref "R47") (pin "2") (pinfunction "2_2") (pintype "passive"))
      (node (ref "S2") (pin "10") (pinfunction "10_10") (pintype "passive"))
    )
    (net (code "128") (name "V+") (class "Default")
      (node (ref "B2") (pin "+") (pinfunction "+_+") (pintype "passive"))
      (node (ref "C1") (pin "+") (pinfunction "+_+") (pintype "passive"))
      (node (ref "IC9") (pin "IN") (pinfunction "IN_IN") (pintype "input"))
    )
    (net (code "129") (name "VCC") (class "Default")
      (node (ref "C2") (pin "+") (pinfunction "+_+") (pintype "passive"))
      (node (ref "C4") (pin "2") (pinfunction "2_2") (pintype "passive"))
      (node (ref "D1") (pin "A") (pinfunction "A_A") (pintype "passive"))
      (node (ref "IC7") (pin "18") (pinfunction "AVCC_18") (pintype "power_in"))
      (node (ref "IC7") (pin "4") (pinfunction "VCC_4") (pintype "power_in"))
      (node (ref "IC7") (pin "6") (pinfunction "VCC_6") (pintype "power_in"))
      (node (ref "IC8") (pin "8") (pinfunction "VCC_8") (pintype "power_in"))
      (node (ref "IC9") (pin "OUT") (pinfunction "OUT_OUT") (pintype "passive"))
      (node (ref "J1") (pin "5") (pinfunction "S_5") (pintype "passive"))
      (node (ref "R1") (pin "2") (pinfunction "2_2") (pintype "passive"))
      (node (ref "R48") (pin "2") (pinfunction "2_2") (pintype "passive"))
      (node (ref "R49") (pin "2") (pinfunction "2_2") (pintype "passive"))
    )
    (net (code "130") (name "unconnected-(G1-+-Pad+@1)") (class "Default")
      (node (ref "G1") (pin "+@1") (pinfunction "+_+@1") (pintype "passive"))
    )
    (net (code "131") (name "unconnected-(IC1-H1A-CO-Pad12)") (class "Default")
      (node (ref "IC1-H1") (pin "12") (pinfunction "CO_12") (pintype "output"))
    )
    (net (code "132") (name "unconnected-(IC1-H1A-Q4-Pad10)") (class "Default")
      (node (ref "IC1-H1") (pin "10") (pinfunction "Q4_10") (pintype "output"))
    )
    (net (code "133") (name "unconnected-(IC1-H1A-Q5-Pad1)") (class "Default")
      (node (ref "IC1-H1") (pin "1") (pinfunction "Q5_1") (pintype "output"))
    )
    (net (code "134") (name "unconnected-(IC1-H1A-Q6-Pad5)") (class "Default")
      (node (ref "IC1-H1") (pin "5") (pinfunction "Q6_5") (pintype "output"))
    )
    (net (code "135") (name "unconnected-(IC1-H1A-Q7-Pad6)") (class "Default")
      (node (ref "IC1-H1") (pin "6") (pinfunction "Q7_6") (pintype "output"))
    )
    (net (code "136") (name "unconnected-(IC1-H1A-Q8-Pad9)") (class "Default")
      (node (ref "IC1-H1") (pin "9") (pinfunction "Q8_9") (pintype "output"))
    )
    (net (code "137") (name "unconnected-(IC1-H1A-Q9-Pad11)") (class "Default")
      (node (ref "IC1-H1") (pin "11") (pinfunction "Q9_11") (pintype "output"))
    )
    (net (code "138") (name "unconnected-(IC2-H2A-CO-Pad12)") (class "Default")
      (node (ref "IC2-H2") (pin "12") (pinfunction "CO_12") (pintype "output"))
    )
    (net (code "139") (name "unconnected-(IC3-M1A-CO-Pad12)") (class "Default")
      (node (ref "IC3-M1") (pin "12") (pinfunction "CO_12") (pintype "output"))
    )
    (net (code "140") (name "unconnected-(IC3-M1A-Q7-Pad6)") (class "Default")
      (node (ref "IC3-M1") (pin "6") (pinfunction "Q7_6") (pintype "output"))
    )
    (net (code "141") (name "unconnected-(IC3-M1A-Q8-Pad9)") (class "Default")
      (node (ref "IC3-M1") (pin "9") (pinfunction "Q8_9") (pintype "output"))
    )
    (net (code "142") (name "unconnected-(IC3-M1A-Q9-Pad11)") (class "Default")
      (node (ref "IC3-M1") (pin "11") (pinfunction "Q9_11") (pintype "output"))
    )
    (net (code "143") (name "unconnected-(IC4-M2A-CO-Pad12)") (class "Default")
      (node (ref "IC4-M2") (pin "12") (pinfunction "CO_12") (pintype "output"))
    )
    (net (code "144") (name "unconnected-(IC5-S1A-CO-Pad12)") (class "Default")
      (node (ref "IC5-S1") (pin "12") (pinfunction "CO_12") (pintype "output"))
    )
    (net (code "145") (name "unconnected-(IC5-S1A-Q7-Pad6)") (class "Default")
      (node (ref "IC5-S1") (pin "6") (pinfunction "Q7_6") (pintype "output"))
    )
    (net (code "146") (name "unconnected-(IC5-S1A-Q8-Pad9)") (class "Default")
      (node (ref "IC5-S1") (pin "9") (pinfunction "Q8_9") (pintype "output"))
    )
    (net (code "147") (name "unconnected-(IC5-S1A-Q9-Pad11)") (class "Default")
      (node (ref "IC5-S1") (pin "11") (pinfunction "Q9_11") (pintype "output"))
    )
    (net (code "148") (name "unconnected-(IC6-S2A-CO-Pad12)") (class "Default")
      (node (ref "IC6-S2") (pin "12") (pinfunction "CO_12") (pintype "output"))
    )
    (net (code "149") (name "unconnected-(IC7-ADC6-Pad19)") (class "Default")
      (node (ref "IC7") (pin "19") (pinfunction "ADC6_19") (pintype "bidirectional"))
    )
    (net (code "150") (name "unconnected-(IC7-ADC7-Pad22)") (class "Default")
      (node (ref "IC7") (pin "22") (pinfunction "ADC7_22") (pintype "bidirectional"))
    )
    (net (code "151") (name "unconnected-(IC7-AREF-Pad20)") (class "Default")
      (node (ref "IC7") (pin "20") (pinfunction "AREF_20") (pintype "passive"))
    )
    (net (code "152") (name "unconnected-(IC8-SQW{slash}OUT-Pad7)") (class "Default")
      (node (ref "IC8") (pin "7") (pinfunction "SQW/OUT_7") (pintype "bidirectional"))
    )
  )
)
